# 07_ADC.net
KiCad netlist of a schematic drawn in Altium Designer
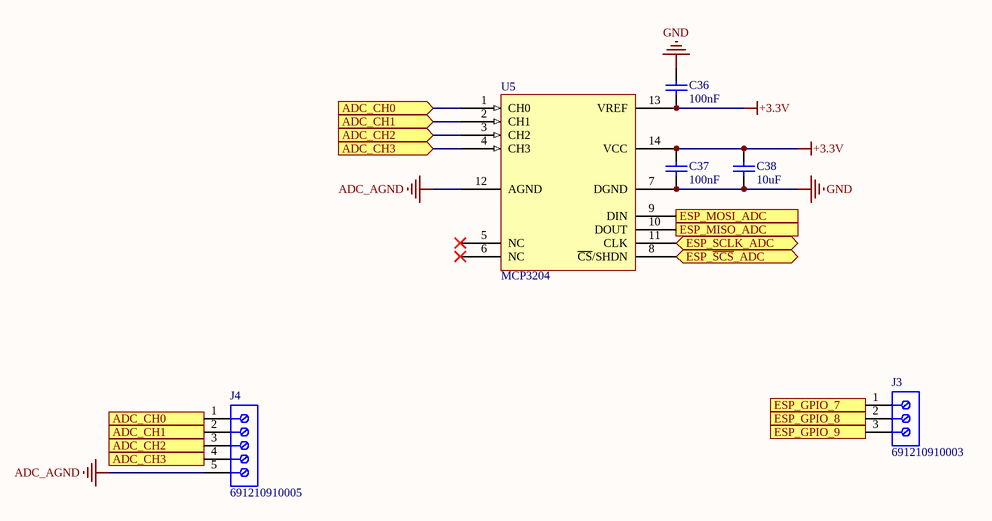
[diagram p0: 07_ADC.SchDoc]

(export (version "E")
  (design (tool "Eeschema 10.0.6"))
  (components
    (comp (ref "C36")
      (value "100nF")
      (footprint "C0402")
      (fields (field (name "Comment") "Capacitor"))
      (libsource (lib "MiclsLib") (part "Capacitor"))
    )
    (comp (ref "C37")
      (value "100nF")
      (footprint "C0402")
      (fields (field (name "Comment") "Capacitor"))
      (libsource (lib "MiclsLib") (part "Capacitor"))
    )
    (comp (ref "C38")
      (value "10uF")
      (footprint "C0402")
      (fields (field (name "Comment") "Capacitor"))
      (libsource (lib "MiclsLib") (part "Capacitor"))
    )
    (comp (ref "J3")
      (value "691210910003")
      (footprint "691210910003")
      (description "WR-TBL Serie 2109 Horizontal Entry, Rising Cage Clamp, pitch 2.54mm, 3p")
      (fields (field (name "PUBLISHER") "Wurth Elektronik"))
      (libsource (lib "691322310002.") (part "691210910003"))
    )
    (comp (ref "J4")
      (value "691210910005")
      (footprint "691210910005")
      (description "WR-TBL Serie 2109 Horizontal Entry, Rising Cage Clamp, pitch 2.54mm, 5p")
      (fields (field (name "PUBLISHER") "Wurth Elektronik"))
      (libsource (lib "691322310002.") (part "691210910005"))
    )
    (comp (ref "U5")
      (value "MCP3204")
      (footprint "MCP3204-14N")
      (libsource (lib "MiclsLib") (part "MCP3204"))
    )
  )
  (nets
    (net (code "1") (name "+3.3V") (class "Default")
      (node (ref "C36") (pin "1") (pinfunction "1_1") (pintype "passive"))
      (node (ref "C37") (pin "2") (pinfunction "2_2") (pintype "passive"))
      (node (ref "C38") (pin "2") (pinfunction "2_2") (pintype "passive"))
      (node (ref "U5") (pin "13") (pinfunction "VREF_13") (pintype "passive"))
      (node (ref "U5") (pin "14") (pinfunction "VCC_14") (pintype "passive"))
    )
    (net (code "2") (name "/ADC_CH0") (class "Default")
      (node (ref "J4") (pin "1") (pinfunction "1_1") (pintype "passive"))
      (node (ref "U5") (pin "1") (pinfunction "CH0_1") (pintype "input"))
    )
    (net (code "3") (name "/ADC_CH1") (class "Default")
      (node (ref "J4") (pin "2") (pinfunction "2_2") (pintype "passive"))
      (node (ref "U5") (pin "2") (pinfunction "CH1_2") (pintype "input"))
    )
    (net (code "4") (name "/ADC_CH2") (class "Default")
      (node (ref "J4") (pin "3") (pinfunction "3_3") (pintype "passive"))
      (node (ref "U5") (pin "3") (pinfunction "CH2_3") (pintype "input"))
    )
    (net (code "5") (name "/ADC_CH3") (class "Default")
      (node (ref "J4") (pin "4") (pinfunction "4_4") (pintype "passive"))
      (node (ref "U5") (pin "4") (pinfunction "CH3_4") (pintype "input"))
    )
    (net (code "6") (name "/ESP_GPIO_7") (class "Default")
      (node (ref "J3") (pin "1") (pinfunction "1_1") (pintype "passive"))
    )
    (net (code "7") (name "/ESP_GPIO_8") (class "Default")
      (node (ref "J3") (pin "2") (pinfunction "2_2") (pintype "passive"))
    )
    (net (code "8") (name "/ESP_GPIO_9") (class "Default")
      (node (ref "J3") (pin "3") (pinfunction "3_3") (pintype "passive"))
    )
    (net (code "9") (name "/ESP_MISO_ADC") (class "Default")
      (node (ref "U5") (pin "10") (pinfunction "DOUT_10") (pintype "passive"))
    )
    (net (code "10") (name "/ESP_MOSI_ADC") (class "Default")
      (node (ref "U5") (pin "9") (pinfunction "DIN_9") (pintype "passive"))
    )
    (net (code "11") (name "/ESP_SCLK_ADC") (class "Default")
      (node (ref "U5") (pin "11") (pinfunction "CLK_11") (pintype "passive"))
    )
    (net (code "12") (name "/ESP_~{SCS}_ADC") (class "Default")
      (node (ref "U5") (pin "8") (pinfunction "~{CS}/SHDN_8") (pintype "passive"))
    )
    (net (code "13") (name "ADC_AGND") (class "Default")
      (node (ref "J4") (pin "5") (pinfunction "5_5") (pintype "passive"))
      (node (ref "U5") (pin "12") (pinfunction "AGND_12") (pintype "passive"))
    )
    (net (code "14") (name "GND") (class "Default")
      (node (ref "C36") (pin "2") (pinfunction "2_2") (pintype "passive"))
      (node (ref "C37") (pin "1") (pinfunction "1_1") (pintype "passive"))
      (node (ref "C38") (pin "1") (pinfunction "1_1") (pintype "passive"))
      (node (ref "U5") (pin "7") (pinfunction "DGND_7") (pintype "passive"))
    )
    (net (code "15") (name "unconnected-(U5-NC-Pad5)") (class "Default")
      (node (ref "U5") (pin "5") (pinfunction "NC_5") (pintype "passive+no_connect"))
    )
    (net (code "16") (name "unconnected-(U5-NC-Pad6)") (class "Default")
      (node (ref "U5") (pin "6") (pinfunction "NC_6") (pintype "passive+no_connect"))
    )
  )
)
